# AMU-S13-V00-BSPDShutdownRelay.net
KiCad netlist of a schematic drawn in Altium Designer
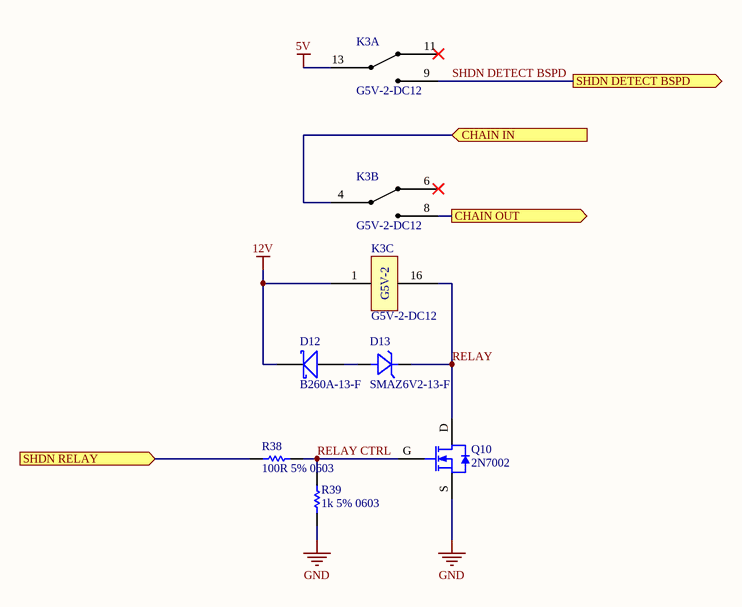
[diagram p0: AMU-S13-V00-BSPDShutdownRelay.SchDoc]

(export (version "E")
  (design (tool "Eeschema 10.0.6"))
  (components
    (comp (ref "D12")
      (value "B260A-13-F")
      (footprint "SMA")
      (description "Diode, Schottky Barrier Rectifier, 60 V, 2 A, B260A-13-F")
      (libsource (lib "QUTMS_DiodeLibrary") (part "B260A-13-F"))
    )
    (comp (ref "D13")
      (value "SMAZ6V2-13-F")
      (footprint "SMA")
      (description "Zener Diode 6.2V 1W ±5% Surface Mount SMA")
      (fields (field (name "MANUFACTURER") "Generic") (field (name "MPN") "5V6 500mW SMA"))
      (libsource (lib "QUTMS_DiodeLibrary") (part "SMAZ6V2-13-F"))
    )
    (comp (ref "K3")
      (value "G5V-2-DC12")
      (footprint "G5V-2")
      (description "General Purpose Relay DPDT (2 Form C) Through Hole, 12V, 2A")
      (libsource (lib "QUTMS_RelayLibrary") (part "G5V-2-DC12"))
    )
    (comp (ref "Q10")
      (value "2N7002")
      (footprint "SOT23-3")
      (libsource (lib "QUTMS_MOSFETLibrary") (part "2N7002"))
    )
    (comp (ref "R38")
      (value "100R 5% 0603")
      (footprint "Res_ThinFilm_0603")
      (description "Resistor, SMD, 100R, 0.1W, 5%, 0603")
      (libsource (lib "StandardResistors") (part "100R 5%, 0603"))
    )
    (comp (ref "R39")
      (value "1k 5% 0603")
      (footprint "Res_ThinFilm_0603")
      (description "Resistor, SMD, 1k, 0.1W, 5%, 0603")
      (libsource (lib "StandardResistors") (part "1k 5% 0603"))
    )
  )
  (nets
    (net (code "1") (name "/CHAIN IN") (class "Default")
      (node (ref "K3") (pin "4") (pinfunction "4_4") (pintype "passive"))
    )
    (net (code "2") (name "/CHAIN OUT") (class "Default")
      (node (ref "K3") (pin "8") (pinfunction "8_8") (pintype "passive"))
    )
    (net (code "3") (name "/RELAY") (class "Default")
      (node (ref "D13") (pin "K") (pinfunction "Cathode_K") (pintype "passive"))
      (node (ref "K3") (pin "16") (pinfunction "16_16") (pintype "passive"))
      (node (ref "Q10") (pin "D") (pinfunction "D_D") (pintype "passive"))
    )
    (net (code "4") (name "/RELAY CTRL") (class "Default")
      (node (ref "Q10") (pin "G") (pinfunction "G_G") (pintype "passive"))
      (node (ref "R38") (pin "2") (pinfunction "2_2") (pintype "passive"))
      (node (ref "R39") (pin "2") (pinfunction "2_2") (pintype "passive"))
    )
    (net (code "5") (name "/SHDN DETECT BSPD") (class "Default")
      (node (ref "K3") (pin "9") (pinfunction "9_9") (pintype "passive"))
    )
    (net (code "6") (name "/SHDN RELAY") (class "Default")
      (node (ref "R38") (pin "1") (pinfunction "1_1") (pintype "passive"))
    )
    (net (code "7") (name "5V") (class "Default")
      (node (ref "K3") (pin "13") (pinfunction "13_13") (pintype "passive"))
    )
    (net (code "8") (name "12V") (class "Default")
      (node (ref "D12") (pin "K") (pinfunction "K_K") (pintype "passive"))
      (node (ref "K3") (pin "1") (pinfunction "1_1") (pintype "passive"))
    )
    (net (code "9") (name "GND") (class "Default")
      (node (ref "Q10") (pin "S") (pinfunction "S_S") (pintype "passive"))
      (node (ref "R39") (pin "1") (pinfunction "1_1") (pintype "passive"))
    )
    (net (code "10") (name "Net-(D13-Anode)") (class "Default")
      (node (ref "D12") (pin "A") (pinfunction "A_A") (pintype "passive"))
      (node (ref "D13") (pin "A") (pinfunction "Anode_A") (pintype "passive"))
    )
    (net (code "11") (name "unconnected-(K3-Pad6)") (class "Default")
      (node (ref "K3") (pin "6") (pinfunction "6_6") (pintype "passive+no_connect"))
    )
    (net (code "12") (name "unconnected-(K3-Pad11)") (class "Default")
      (node (ref "K3") (pin "11") (pinfunction "11_11") (pintype "passive+no_connect"))
    )
  )
)
